# IMU.net
KiCad netlist of a schematic drawn in EAGLE
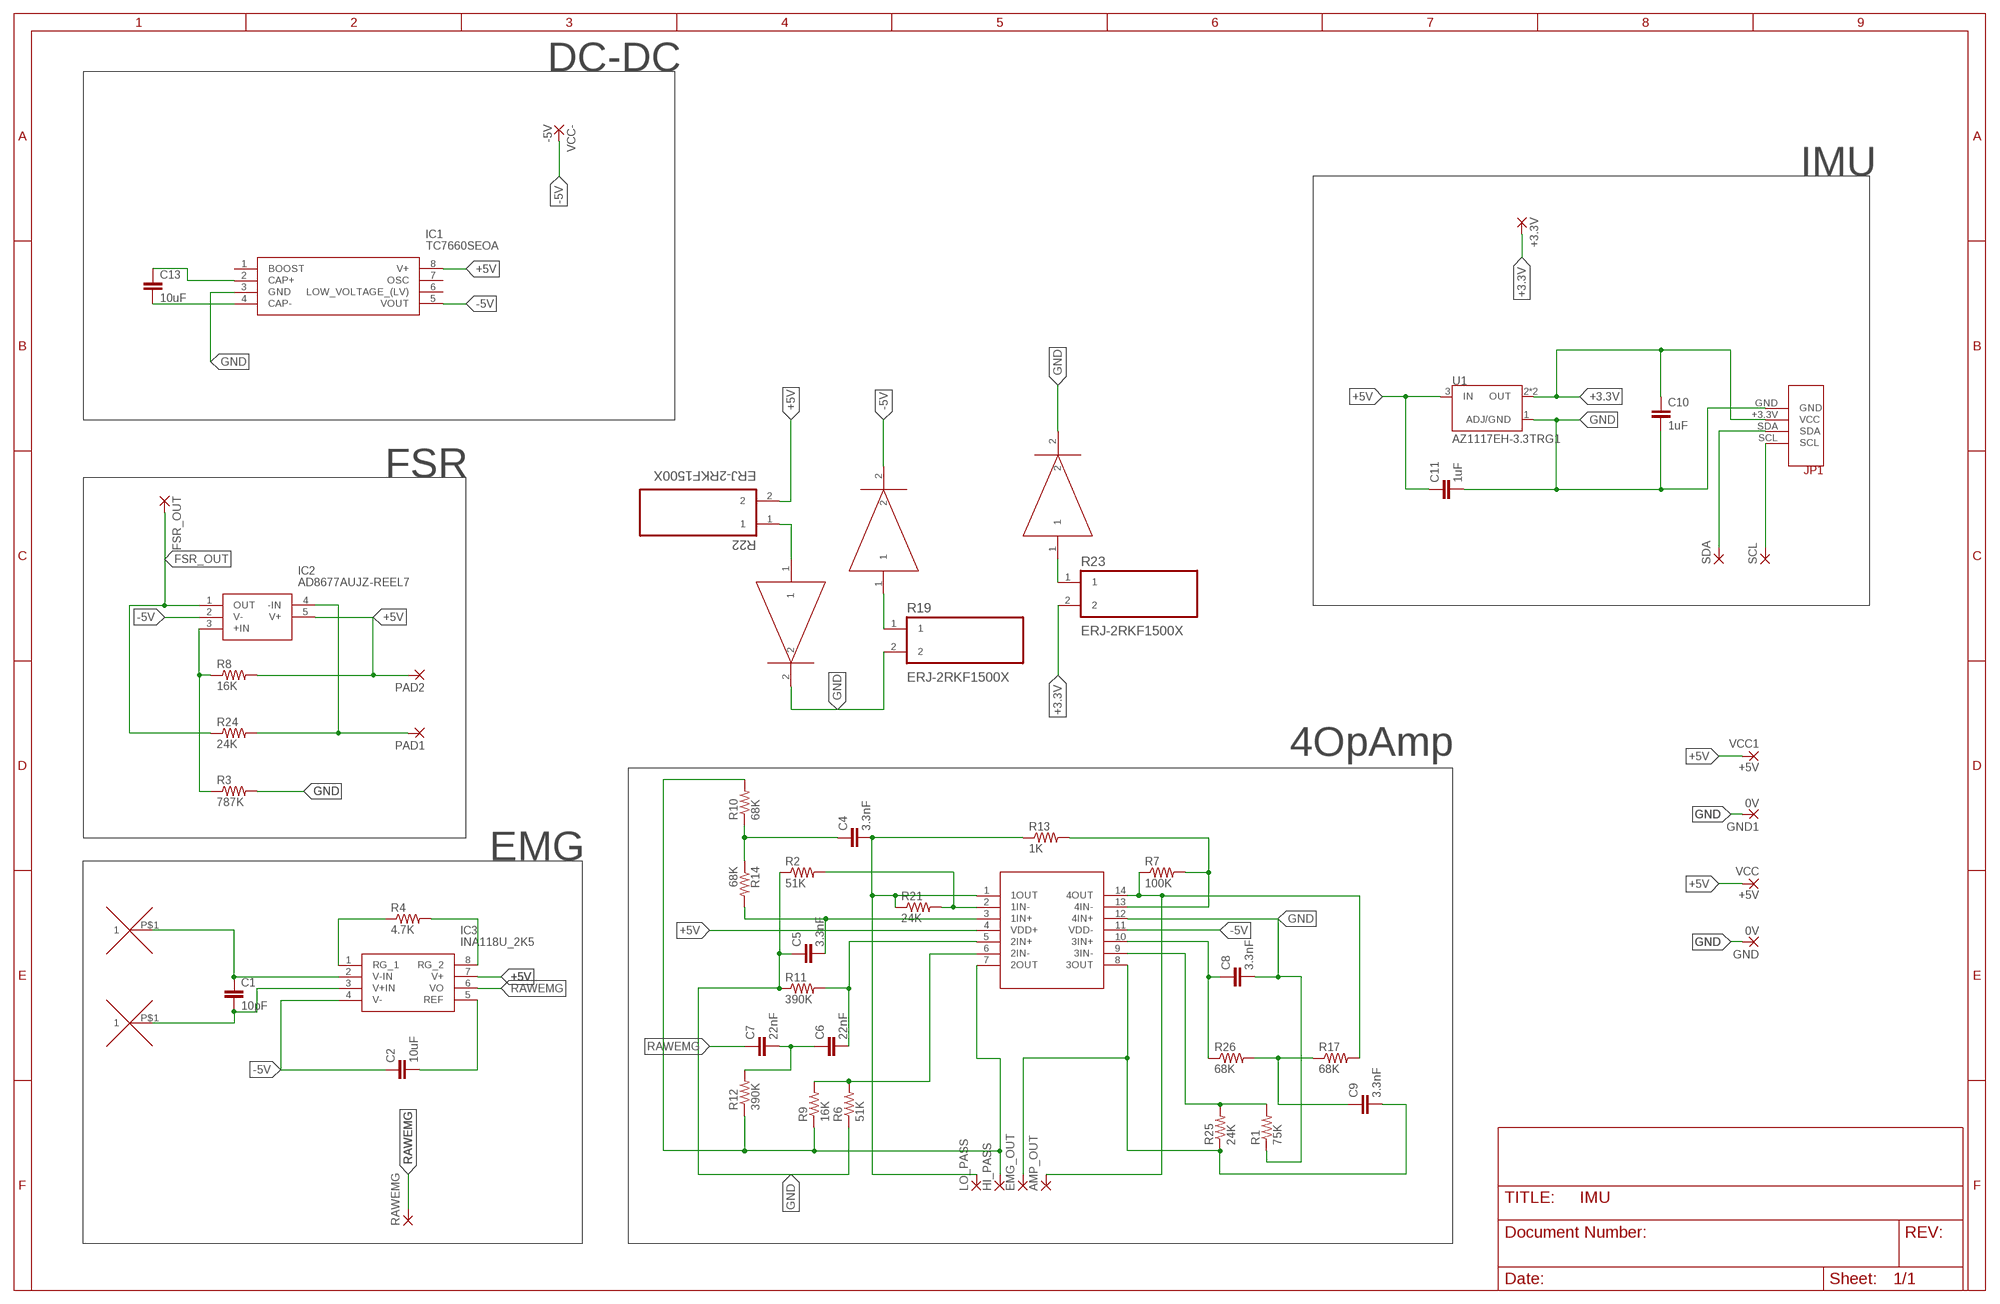
[diagram p0: schematic, sheet 1]

(export (version "E")
  (design (tool "Eeschema 10.0.6"))
  (components
    (comp (ref "+3.3V")
      (value "1,6/0,8")
      (footprint "eagle-import:1,6_0,8")
      (libsource (lib "eagle-import") (part "wirepad_412_1,6/0,8"))
    )
    (comp (ref "AMP_OUT")
      (value "1,6/0,8")
      (footprint "eagle-import:1,6_0,8")
      (libsource (lib "eagle-import") (part "1,6/0,8"))
    )
    (comp (ref "BLUE")
      (value "RESC0402X40N")
      (footprint "eagle-import:RESC0402X40N")
      (fields (field (name "MANUFACTURER") "KOA"))
      (libsource (lib "eagle-import") (part "RESC0402X40N"))
    )
    (comp (ref "C1")
      (value "10pF")
      (footprint "eagle-import:HPC0201")
      (libsource (lib "eagle-import") (part "rcl_334_C-EUHPC0201"))
    )
    (comp (ref "C2")
      (value "10uF")
      (footprint "eagle-import:C0805")
      (libsource (lib "eagle-import") (part "rcl_334_C-EUC0805"))
    )
    (comp (ref "C4")
      (value "3.3nF")
      (footprint "eagle-import:C1206")
      (libsource (lib "eagle-import") (part "C-EUC1206"))
    )
    (comp (ref "C5")
      (value "3.3nF")
      (footprint "eagle-import:C1206")
      (libsource (lib "eagle-import") (part "C-EUC1206"))
    )
    (comp (ref "C6")
      (value "22nF")
      (footprint "eagle-import:C0805")
      (libsource (lib "eagle-import") (part "C-EUC0805"))
    )
    (comp (ref "C7")
      (value "22nF")
      (footprint "eagle-import:C0805")
      (libsource (lib "eagle-import") (part "C-EUC0805"))
    )
    (comp (ref "C8")
      (value "3.3nF")
      (footprint "eagle-import:C1206")
      (libsource (lib "eagle-import") (part "C-EUC1206"))
    )
    (comp (ref "C9")
      (value "3.3nF")
      (footprint "eagle-import:C1206")
      (libsource (lib "eagle-import") (part "C-EUC1206"))
    )
    (comp (ref "C10")
      (value "1uF")
      (footprint "eagle-import:C0402")
      (libsource (lib "eagle-import") (part "rcl_334_C-EUC0402"))
    )
    (comp (ref "C11")
      (value "1uF")
      (footprint "eagle-import:C0402")
      (libsource (lib "eagle-import") (part "rcl_334_C-EUC0402"))
    )
    (comp (ref "C13")
      (value "10uF")
      (footprint "eagle-import:C0805K")
      (libsource (lib "eagle-import") (part "rcl_334_C-EUC0805K"))
    )
    (comp (ref "EMG_OUT")
      (value "1,6/0,8")
      (footprint "eagle-import:1,6_0,8")
      (libsource (lib "eagle-import") (part "1,6/0,8"))
    )
    (comp (ref "FSR_OUT")
      (value "1,6/0,8")
      (footprint "eagle-import:1,6_0,8")
      (libsource (lib "eagle-import") (part "1,6/0,8"))
    )
    (comp (ref "GND")
      (value "0V")
      (footprint "eagle-import:1,6_0,8")
      (libsource (lib "eagle-import") (part "1,6/0,8"))
    )
    (comp (ref "GND1")
      (value "0V")
      (footprint "eagle-import:1,6_0,8")
      (libsource (lib "eagle-import") (part "1,6/0,8"))
    )
    (comp (ref "HI_PASS")
      (value "1,6/0,8")
      (footprint "eagle-import:1,6_0,8")
      (libsource (lib "eagle-import") (part "1,6/0,8"))
    )
    (comp (ref "IC1")
      (value "TC7660SEOA")
      (footprint "eagle-import:SOIC127P600X175-8N")
      (fields (field (name "MOUSER_PART_NUMBER") "579-TC7660SEOA"))
      (libsource (lib "eagle-import") (part "TC7660SEOA"))
    )
    (comp (ref "IC2")
      (value "AD8677AUJZ-REEL7")
      (footprint "eagle-import:SOT95P280X100-5N")
      (fields (field (name "MOUSER_PART_NUMBER") "584-AD8677AUJZ-R7"))
      (libsource (lib "eagle-import") (part "AD8677AUJZ-REEL7"))
    )
    (comp (ref "IC3")
      (value "INA118U_2K5")
      (footprint "eagle-import:SOIC127P600X175-8N")
      (fields
        (field (name "ARROW_PART_NUMBER") "INA118U/2K5")
        (field (name "MOUSER_PART_NUMBER") "595-INA118U/2K5")
      )
      (libsource (lib "eagle-import") (part "INA118U_2K5"))
    )
    (comp (ref "IMU")
      (value "IMU")
      (footprint "eagle-import:IMU")
      (libsource (lib "eagle-import") (part "IMU"))
    )
    (comp (ref "LO_PASS")
      (value "1,6/0,8")
      (footprint "eagle-import:1,6_0,8")
      (libsource (lib "eagle-import") (part "1,6/0,8"))
    )
    (comp (ref "ORANGE")
      (value "RESC0402X40N")
      (footprint "eagle-import:RESC0402X40N")
      (fields (field (name "MANUFACTURER") "KOA"))
      (libsource (lib "eagle-import") (part "RESC0402X40N"))
    )
    (comp (ref "PAD1")
      (value "SMD2")
      (footprint "eagle-import:SMD1,27-2,54")
      (libsource (lib "eagle-import") (part "SMD2"))
    )
    (comp (ref "PAD2")
      (value "SMD2")
      (footprint "eagle-import:SMD1,27-2,54")
      (libsource (lib "eagle-import") (part "SMD2"))
    )
    (comp (ref "R1")
      (value "75K")
      (footprint "eagle-import:R0402")
      (libsource (lib "eagle-import") (part "adafruit_420_R-US_R0402"))
    )
    (comp (ref "R2")
      (value "51K")
      (footprint "eagle-import:R0402")
      (libsource (lib "eagle-import") (part "adafruit_420_R-US_R0402"))
    )
    (comp (ref "R3")
      (value "787K")
      (footprint "eagle-import:R0805")
      (libsource (lib "eagle-import") (part "rcl_R-US_R0805"))
    )
    (comp (ref "R4")
      (value "4.7K")
      (footprint "eagle-import:R0402")
      (libsource (lib "eagle-import") (part "adafruit@1_R-US_R0402"))
    )
    (comp (ref "R6")
      (value "51K")
      (footprint "eagle-import:R0402")
      (libsource (lib "eagle-import") (part "adafruit_420_R-US_R0402"))
    )
    (comp (ref "R7")
      (value "100K")
      (footprint "eagle-import:R1005")
      (libsource (lib "eagle-import") (part "adafruit@1_R-US_R1005"))
    )
    (comp (ref "R8")
      (value "16K")
      (footprint "eagle-import:R0402")
      (libsource (lib "eagle-import") (part "adafruit_420_R-US_R0402"))
    )
    (comp (ref "R9")
      (value "16K")
      (footprint "eagle-import:R0402")
      (libsource (lib "eagle-import") (part "adafruit_420_R-US_R0402"))
    )
    (comp (ref "R10")
      (value "68K")
      (footprint "eagle-import:R0402")
      (libsource (lib "eagle-import") (part "adafruit_420_R-US_R0402"))
    )
    (comp (ref "R11")
      (value "390K")
      (footprint "eagle-import:R0603")
      (libsource (lib "eagle-import") (part "R-US_R0603"))
    )
    (comp (ref "R12")
      (value "390K")
      (footprint "eagle-import:R0603")
      (libsource (lib "eagle-import") (part "adafruit@1_R-US_R0603"))
    )
    (comp (ref "R13")
      (value "1K")
      (footprint "eagle-import:R0402")
      (libsource (lib "eagle-import") (part "adafruit_420_R-US_R0402"))
    )
    (comp (ref "R14")
      (value "68K")
      (footprint "eagle-import:R0402")
      (libsource (lib "eagle-import") (part "adafruit_420_R-US_R0402"))
    )
    (comp (ref "R17")
      (value "68K")
      (footprint "eagle-import:R0402")
      (libsource (lib "eagle-import") (part "adafruit_420_R-US_R0402"))
    )
    (comp (ref "R19")
      (value "ERJ-2RKF1500X")
      (footprint "eagle-import:RESC1005X40N")
      (fields (field (name "DIGI-KEY_PART_NUMBER") "P150LCT-ND") (field (name "MF") "Panasonic Electronic"))
      (libsource (lib "eagle-import") (part "ERJ-2RKF1500X"))
    )
    (comp (ref "R21")
      (value "24K")
      (footprint "eagle-import:R0402")
      (libsource (lib "eagle-import") (part "adafruit_420_R-US_R0402"))
    )
    (comp (ref "R22")
      (value "ERJ-2RKF1500X")
      (footprint "eagle-import:RESC1005X40N")
      (fields (field (name "DIGI-KEY_PART_NUMBER") "P150LCT-ND") (field (name "MF") "Panasonic Electronic"))
      (libsource (lib "eagle-import") (part "ERJ-2RKF1500X"))
    )
    (comp (ref "R23")
      (value "ERJ-2RKF1500X")
      (footprint "eagle-import:RESC1005X40N")
      (fields (field (name "DIGI-KEY_PART_NUMBER") "P150LCT-ND") (field (name "MF") "Panasonic Electronic"))
      (libsource (lib "eagle-import") (part "ERJ-2RKF1500X"))
    )
    (comp (ref "R24")
      (value "24K")
      (footprint "eagle-import:R0402")
      (libsource (lib "eagle-import") (part "adafruit_420_R-US_R0402"))
    )
    (comp (ref "R25")
      (value "24K")
      (footprint "eagle-import:R0402")
      (libsource (lib "eagle-import") (part "adafruit_420_R-US_R0402"))
    )
    (comp (ref "R26")
      (value "68K")
      (footprint "eagle-import:R0402")
      (libsource (lib "eagle-import") (part "adafruit_420_R-US_R0402"))
    )
    (comp (ref "RAWEMG")
      (value "1,6/0,8")
      (footprint "eagle-import:1,6_0,8")
      (libsource (lib "eagle-import") (part "1,6/0,8"))
    )
    (comp (ref "RED")
      (value "RESC0402X40N")
      (footprint "eagle-import:RESC0402X40N")
      (fields (field (name "MANUFACTURER") "KOA"))
      (libsource (lib "eagle-import") (part "RESC0402X40N"))
    )
    (comp (ref "SCL")
      (value "1,6/0,8")
      (footprint "eagle-import:1,6_0,8")
      (libsource (lib "eagle-import") (part "wirepad_412_1,6/0,8"))
    )
    (comp (ref "SDA")
      (value "1,6/0,8")
      (footprint "eagle-import:1,6_0,8")
      (libsource (lib "eagle-import") (part "wirepad_412_1,6/0,8"))
    )
    (comp (ref "U$1")
      (value "TLC2274-HT")
      (footprint "eagle-import:SOP65P640X120-14N")
      (libsource (lib "eagle-import") (part "TLC2274-HT"))
    )
    (comp (ref "U$2")
      (value "EMG_VIA")
      (footprint "eagle-import:EMG_VIA")
      (libsource (lib "eagle-import") (part "EMG_VIA"))
    )
    (comp (ref "U$3")
      (value "EMG_VIA")
      (footprint "eagle-import:EMG_VIA")
      (libsource (lib "eagle-import") (part "EMG_VIA"))
    )
    (comp (ref "U1")
      (value "AZ1117EH-3.3TRG1")
      (footprint "eagle-import:SOT230P700X180-4N")
      (fields
        (field (name "DIGI-KEY_PART_NUMBER") "AZ1117EH-3.3TRG1DICT-ND")
        (field (name "MF") "Diodes Inc.")
      )
      (libsource (lib "eagle-import") (part "AZ1117EH-3.3TRG1"))
    )
    (comp (ref "VCC")
      (value "+5V")
      (footprint "eagle-import:1,6_0,8")
      (libsource (lib "eagle-import") (part "1,6/0,8"))
    )
    (comp (ref "VCC-")
      (value "-5V")
      (footprint "eagle-import:1,6_0,8")
      (libsource (lib "eagle-import") (part "1,6/0,8"))
    )
    (comp (ref "VCC1")
      (value "+5V")
      (footprint "eagle-import:1,6_0,8")
      (libsource (lib "eagle-import") (part "1,6/0,8"))
    )
  )
  (nets
    (net (code "1") (name "+3.3V") (class "Default")
      (node (ref "+3.3V") (pin "1") (pinfunction "P_1") (pintype "passive"))
      (node (ref "C10") (pin "1") (pinfunction "1_1") (pintype "passive"))
      (node (ref "IMU") (pin "+3.3V") (pinfunction "VCC_+3.3V") (pintype "bidirectional"))
      (node (ref "R23") (pin "2") (pinfunction "2_2") (pintype "bidirectional"))
      (node (ref "U1") (pin "2") (pinfunction "OUT_2") (pintype "output"))
      (node (ref "U1") (pin "4") (pinfunction "OUT_4") (pintype "output"))
    )
    (net (code "2") (name "+5V") (class "Default")
      (node (ref "C11") (pin "1") (pinfunction "1_1") (pintype "passive"))
      (node (ref "IC1") (pin "8") (pinfunction "V+_8") (pintype "bidirectional"))
      (node (ref "IC2") (pin "5") (pinfunction "V+_5") (pintype "bidirectional"))
      (node (ref "IC3") (pin "7") (pinfunction "V+_7") (pintype "bidirectional"))
      (node (ref "PAD2") (pin "1") (pinfunction "P_1") (pintype "passive"))
      (node (ref "R22") (pin "2") (pinfunction "2_2") (pintype "bidirectional"))
      (node (ref "R8") (pin "2") (pinfunction "2_2") (pintype "passive"))
      (node (ref "U$1") (pin "4") (pinfunction "VDD+_4") (pintype "bidirectional"))
      (node (ref "U1") (pin "3") (pinfunction "IN_3") (pintype "input"))
      (node (ref "VCC") (pin "1") (pinfunction "P_1") (pintype "passive"))
      (node (ref "VCC1") (pin "1") (pinfunction "P_1") (pintype "passive"))
    )
    (net (code "3") (name "-5V") (class "Default")
      (node (ref "BLUE") (pin "2") (pinfunction "2_2") (pintype "bidirectional"))
      (node (ref "C2") (pin "1") (pinfunction "1_1") (pintype "passive"))
      (node (ref "IC1") (pin "5") (pinfunction "VOUT_5") (pintype "bidirectional"))
      (node (ref "IC2") (pin "2") (pinfunction "V-_2") (pintype "bidirectional"))
      (node (ref "IC3") (pin "4") (pinfunction "V-_4") (pintype "bidirectional"))
      (node (ref "U$1") (pin "11") (pinfunction "VDD-_11") (pintype "bidirectional"))
      (node (ref "VCC-") (pin "1") (pinfunction "P_1") (pintype "passive"))
    )
    (net (code "4") (name "FSR_OUT") (class "Default")
      (node (ref "FSR_OUT") (pin "1") (pinfunction "P_1") (pintype "passive"))
      (node (ref "IC2") (pin "1") (pinfunction "OUT_1") (pintype "output"))
      (node (ref "R24") (pin "1") (pinfunction "1_1") (pintype "passive"))
    )
    (net (code "5") (name "GND") (class "Default")
      (node (ref "C10") (pin "2") (pinfunction "2_2") (pintype "passive"))
      (node (ref "C11") (pin "2") (pinfunction "2_2") (pintype "passive"))
      (node (ref "C5") (pin "1") (pinfunction "1_1") (pintype "passive"))
      (node (ref "C8") (pin "2") (pinfunction "2_2") (pintype "passive"))
      (node (ref "GND") (pin "1") (pinfunction "P_1") (pintype "passive"))
      (node (ref "GND1") (pin "1") (pinfunction "P_1") (pintype "passive"))
      (node (ref "IC1") (pin "3") (pinfunction "GND_3") (pintype "bidirectional"))
      (node (ref "IMU") (pin "GND") (pinfunction "GND_GND") (pintype "bidirectional"))
      (node (ref "ORANGE") (pin "2") (pinfunction "2_2") (pintype "bidirectional"))
      (node (ref "R1") (pin "1") (pinfunction "1_1") (pintype "passive"))
      (node (ref "R11") (pin "1") (pinfunction "1_1") (pintype "passive"))
      (node (ref "R19") (pin "2") (pinfunction "2_2") (pintype "bidirectional"))
      (node (ref "R2") (pin "1") (pinfunction "1_1") (pintype "passive"))
      (node (ref "R3") (pin "2") (pinfunction "2_2") (pintype "passive"))
      (node (ref "R6") (pin "1") (pinfunction "1_1") (pintype "passive"))
      (node (ref "RED") (pin "2") (pinfunction "2_2") (pintype "bidirectional"))
      (node (ref "U$1") (pin "12") (pinfunction "4IN+_12") (pintype "bidirectional"))
      (node (ref "U1") (pin "1") (pinfunction "ADJ/GND_1") (pintype "power_in"))
    )
    (net (code "6") (name "Net-(AMP_OUT-P)") (class "Default")
      (node (ref "AMP_OUT") (pin "1") (pinfunction "P_1") (pintype "passive"))
      (node (ref "R17") (pin "2") (pinfunction "2_2") (pintype "passive"))
      (node (ref "R7") (pin "1") (pinfunction "1_1") (pintype "passive"))
      (node (ref "U$1") (pin "14") (pinfunction "4OUT_14") (pintype "bidirectional"))
    )
    (net (code "7") (name "Net-(BLUE-Pad1)") (class "Default")
      (node (ref "BLUE") (pin "1") (pinfunction "1_1") (pintype "bidirectional"))
      (node (ref "R19") (pin "1") (pinfunction "1_1") (pintype "bidirectional"))
    )
    (net (code "8") (name "Net-(C4-Pad1)") (class "Default")
      (node (ref "C4") (pin "1") (pinfunction "1_1") (pintype "passive"))
      (node (ref "R10") (pin "1") (pinfunction "1_1") (pintype "passive"))
      (node (ref "R14") (pin "1") (pinfunction "1_1") (pintype "passive"))
    )
    (net (code "9") (name "Net-(C6-Pad1)") (class "Default")
      (node (ref "C6") (pin "1") (pinfunction "1_1") (pintype "passive"))
      (node (ref "C7") (pin "2") (pinfunction "2_2") (pintype "passive"))
      (node (ref "R12") (pin "2") (pinfunction "2_2") (pintype "passive"))
    )
    (net (code "10") (name "Net-(C9-Pad1)") (class "Default")
      (node (ref "C9") (pin "1") (pinfunction "1_1") (pintype "passive"))
      (node (ref "R17") (pin "1") (pinfunction "1_1") (pintype "passive"))
      (node (ref "R26") (pin "2") (pinfunction "2_2") (pintype "passive"))
    )
    (net (code "11") (name "Net-(EMG_OUT-P)") (class "Default")
      (node (ref "C9") (pin "2") (pinfunction "2_2") (pintype "passive"))
      (node (ref "EMG_OUT") (pin "1") (pinfunction "P_1") (pintype "passive"))
      (node (ref "R25") (pin "1") (pinfunction "1_1") (pintype "passive"))
      (node (ref "U$1") (pin "8") (pinfunction "3OUT_8") (pintype "bidirectional"))
    )
    (net (code "12") (name "Net-(HI_PASS-P)") (class "Default")
      (node (ref "HI_PASS") (pin "1") (pinfunction "P_1") (pintype "passive"))
      (node (ref "R10") (pin "2") (pinfunction "2_2") (pintype "passive"))
      (node (ref "R12") (pin "1") (pinfunction "1_1") (pintype "passive"))
      (node (ref "R9") (pin "1") (pinfunction "1_1") (pintype "passive"))
      (node (ref "U$1") (pin "7") (pinfunction "2OUT_7") (pintype "bidirectional"))
    )
    (net (code "13") (name "Net-(IC1-CAP+)") (class "Default")
      (node (ref "C13") (pin "1") (pinfunction "1_1") (pintype "passive"))
      (node (ref "IC1") (pin "2") (pinfunction "CAP+_2") (pintype "bidirectional"))
    )
    (net (code "14") (name "Net-(IC1-CAP-)") (class "Default")
      (node (ref "C13") (pin "2") (pinfunction "2_2") (pintype "passive"))
      (node (ref "IC1") (pin "4") (pinfunction "CAP-_4") (pintype "bidirectional"))
    )
    (net (code "15") (name "Net-(IC2-+IN)") (class "Default")
      (node (ref "IC2") (pin "3") (pinfunction "+IN_3") (pintype "input"))
      (node (ref "R3") (pin "1") (pinfunction "1_1") (pintype "passive"))
      (node (ref "R8") (pin "1") (pinfunction "1_1") (pintype "passive"))
    )
    (net (code "16") (name "Net-(IC2--IN)") (class "Default")
      (node (ref "IC2") (pin "4") (pinfunction "-IN_4") (pintype "input"))
      (node (ref "PAD1") (pin "1") (pinfunction "P_1") (pintype "passive"))
      (node (ref "R24") (pin "2") (pinfunction "2_2") (pintype "passive"))
    )
    (net (code "17") (name "Net-(IC3-REF)") (class "Default")
      (node (ref "C2") (pin "2") (pinfunction "2_2") (pintype "passive"))
      (node (ref "IC3") (pin "5") (pinfunction "REF_5") (pintype "bidirectional"))
    )
    (net (code "18") (name "Net-(IC3-RG_1)") (class "Default")
      (node (ref "IC3") (pin "1") (pinfunction "RG_1_1") (pintype "bidirectional"))
      (node (ref "R4") (pin "1") (pinfunction "1_1") (pintype "passive"))
    )
    (net (code "19") (name "Net-(IC3-RG_2)") (class "Default")
      (node (ref "IC3") (pin "8") (pinfunction "RG_2_8") (pintype "bidirectional"))
      (node (ref "R4") (pin "2") (pinfunction "2_2") (pintype "passive"))
    )
    (net (code "20") (name "Net-(IC3-V+IN)") (class "Default")
      (node (ref "C1") (pin "2") (pinfunction "2_2") (pintype "passive"))
      (node (ref "IC3") (pin "3") (pinfunction "V+IN_3") (pintype "bidirectional"))
      (node (ref "U$3") (pin "P$1") (pinfunction "1_P$1") (pintype "bidirectional"))
    )
    (net (code "21") (name "Net-(IC3-V-IN)") (class "Default")
      (node (ref "C1") (pin "1") (pinfunction "1_1") (pintype "passive"))
      (node (ref "IC3") (pin "2") (pinfunction "V-IN_2") (pintype "bidirectional"))
      (node (ref "U$2") (pin "P$1") (pinfunction "1_P$1") (pintype "bidirectional"))
    )
    (net (code "22") (name "Net-(LO_PASS-P)") (class "Default")
      (node (ref "C4") (pin "2") (pinfunction "2_2") (pintype "passive"))
      (node (ref "LO_PASS") (pin "1") (pinfunction "P_1") (pintype "passive"))
      (node (ref "R13") (pin "1") (pinfunction "1_1") (pintype "passive"))
      (node (ref "R21") (pin "1") (pinfunction "1_1") (pintype "passive"))
      (node (ref "U$1") (pin "1") (pinfunction "1OUT_1") (pintype "bidirectional"))
    )
    (net (code "23") (name "Net-(ORANGE-Pad1)") (class "Default")
      (node (ref "ORANGE") (pin "1") (pinfunction "1_1") (pintype "bidirectional"))
      (node (ref "R23") (pin "1") (pinfunction "1_1") (pintype "bidirectional"))
    )
    (net (code "24") (name "Net-(R22-Pad1)") (class "Default")
      (node (ref "R22") (pin "1") (pinfunction "1_1") (pintype "bidirectional"))
      (node (ref "RED") (pin "1") (pinfunction "1_1") (pintype "bidirectional"))
    )
    (net (code "25") (name "Net-(SCL-P)") (class "Default")
      (node (ref "IMU") (pin "SCL") (pinfunction "SCL_SCL") (pintype "bidirectional"))
      (node (ref "SCL") (pin "1") (pinfunction "P_1") (pintype "passive"))
    )
    (net (code "26") (name "Net-(SDA-P)") (class "Default")
      (node (ref "IMU") (pin "SDA") (pinfunction "SDA_SDA") (pintype "bidirectional"))
      (node (ref "SDA") (pin "1") (pinfunction "P_1") (pintype "passive"))
    )
    (net (code "27") (name "Net-(U$1-1IN+)") (class "Default")
      (node (ref "C5") (pin "2") (pinfunction "2_2") (pintype "passive"))
      (node (ref "R14") (pin "2") (pinfunction "2_2") (pintype "passive"))
      (node (ref "U$1") (pin "3") (pinfunction "1IN+_3") (pintype "bidirectional"))
    )
    (net (code "28") (name "Net-(U$1-1IN-)") (class "Default")
      (node (ref "R2") (pin "2") (pinfunction "2_2") (pintype "passive"))
      (node (ref "R21") (pin "2") (pinfunction "2_2") (pintype "passive"))
      (node (ref "U$1") (pin "2") (pinfunction "1IN-_2") (pintype "bidirectional"))
    )
    (net (code "29") (name "Net-(U$1-2IN+)") (class "Default")
      (node (ref "C6") (pin "2") (pinfunction "2_2") (pintype "passive"))
      (node (ref "R11") (pin "2") (pinfunction "2_2") (pintype "passive"))
      (node (ref "U$1") (pin "5") (pinfunction "2IN+_5") (pintype "bidirectional"))
    )
    (net (code "30") (name "Net-(U$1-2IN-)") (class "Default")
      (node (ref "R6") (pin "2") (pinfunction "2_2") (pintype "passive"))
      (node (ref "R9") (pin "2") (pinfunction "2_2") (pintype "passive"))
      (node (ref "U$1") (pin "6") (pinfunction "2IN-_6") (pintype "bidirectional"))
    )
    (net (code "31") (name "Net-(U$1-3IN+)") (class "Default")
      (node (ref "C8") (pin "1") (pinfunction "1_1") (pintype "passive"))
      (node (ref "R26") (pin "1") (pinfunction "1_1") (pintype "passive"))
      (node (ref "U$1") (pin "10") (pinfunction "3IN+_10") (pintype "bidirectional"))
    )
    (net (code "32") (name "Net-(U$1-3IN-)") (class "Default")
      (node (ref "R1") (pin "2") (pinfunction "2_2") (pintype "passive"))
      (node (ref "R25") (pin "2") (pinfunction "2_2") (pintype "passive"))
      (node (ref "U$1") (pin "9") (pinfunction "3IN-_9") (pintype "bidirectional"))
    )
    (net (code "33") (name "Net-(U$1-4IN-)") (class "Default")
      (node (ref "R13") (pin "2") (pinfunction "2_2") (pintype "passive"))
      (node (ref "R7") (pin "2") (pinfunction "2_2") (pintype "passive"))
      (node (ref "U$1") (pin "13") (pinfunction "4IN-_13") (pintype "bidirectional"))
    )
    (net (code "34") (name "RAWEMG") (class "Default")
      (node (ref "C7") (pin "1") (pinfunction "1_1") (pintype "passive"))
      (node (ref "IC3") (pin "6") (pinfunction "VO_6") (pintype "bidirectional"))
      (node (ref "RAWEMG") (pin "1") (pinfunction "P_1") (pintype "passive"))
    )
    (net (code "35") (name "unconnected-(IC1-BOOST-Pad1)") (class "Default")
      (node (ref "IC1") (pin "1") (pinfunction "BOOST_1") (pintype "bidirectional"))
    )
    (net (code "36") (name "unconnected-(IC1-LOW_VOLTAGE_(LV)-Pad6)") (class "Default")
      (node (ref "IC1") (pin "6") (pinfunction "LOW_VOLTAGE_(LV)_6") (pintype "bidirectional"))
    )
    (net (code "37") (name "unconnected-(IC1-OSC-Pad7)") (class "Default")
      (node (ref "IC1") (pin "7") (pinfunction "OSC_7") (pintype "bidirectional"))
    )
  )
)
